# Rat.net
KiCad netlist of a schematic drawn in EAGLE
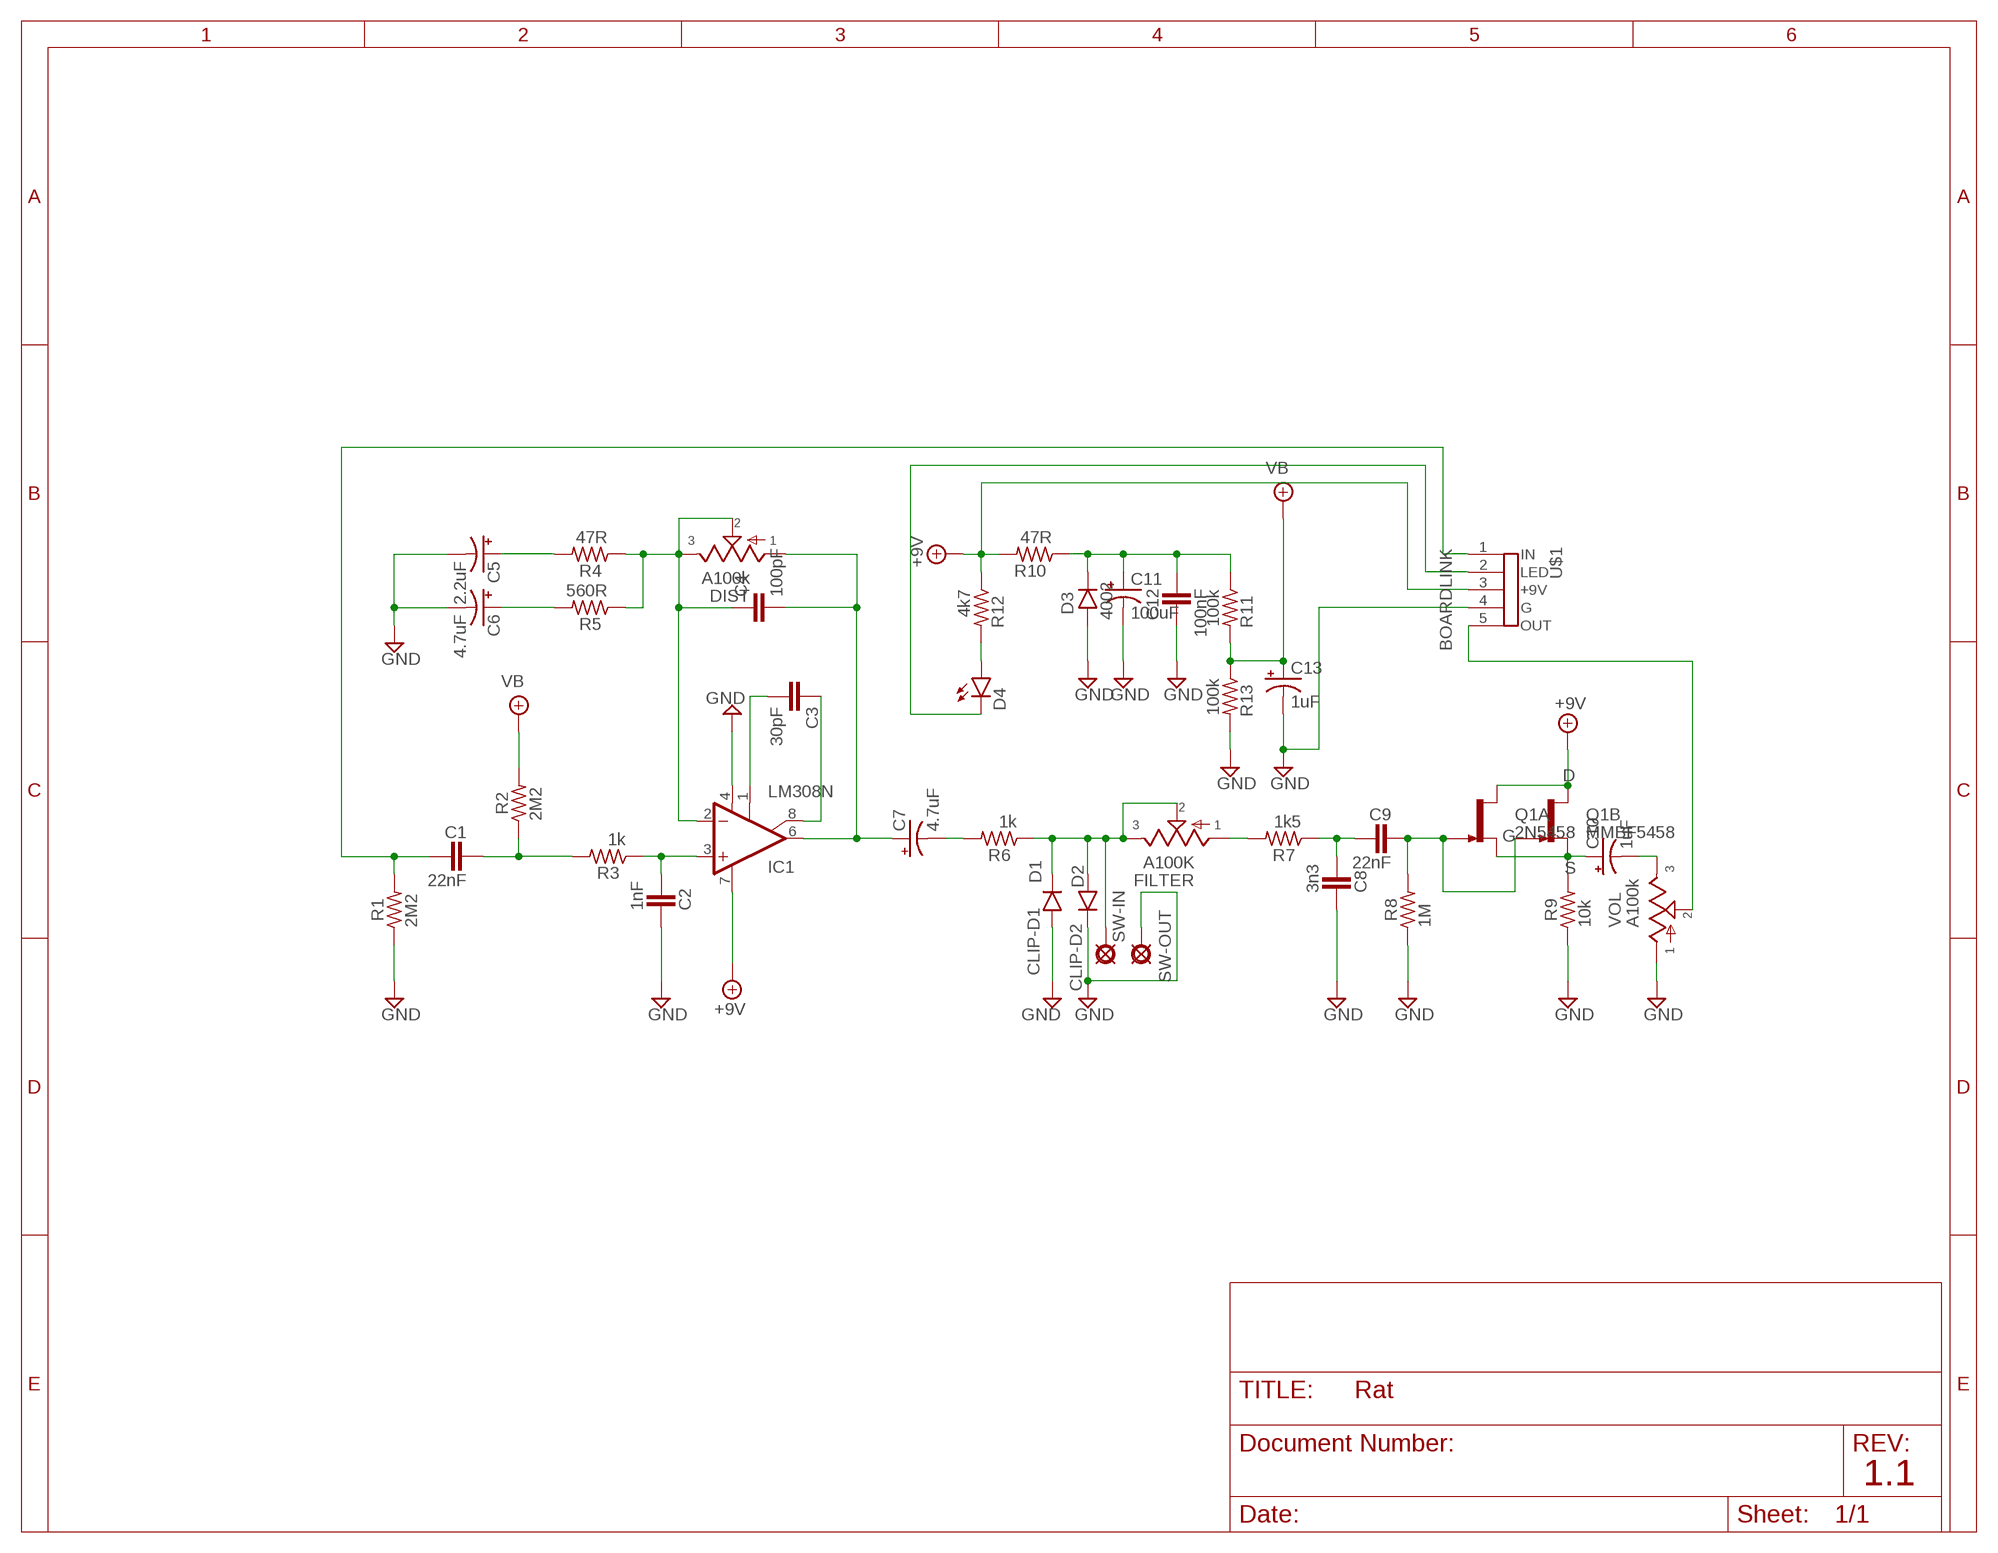
[diagram p0: schematic, sheet 1]

(export (version "E")
  (design (tool "Eeschema 10.0.6"))
  (components
    (comp (ref "C1")
      (value "22nF")
      (footprint "eagle-import:072X025")
      (libsource (lib "eagle-import") (part "072X0252"))
    )
    (comp (ref "C2")
      (value "1nF")
      (footprint "eagle-import:072X025")
      (libsource (lib "eagle-import") (part "072X0252"))
    )
    (comp (ref "C3")
      (value "30pF")
      (footprint "eagle-import:050X030_025")
      (libsource (lib "eagle-import") (part "050X030_0251"))
    )
    (comp (ref "C4")
      (value "100pF")
      (footprint "eagle-import:050X030_025")
      (libsource (lib "eagle-import") (part "050X030_0251"))
    )
    (comp (ref "C5")
      (value "2.2uF")
      (footprint "eagle-import:050_020_1")
      (libsource (lib "eagle-import") (part "0501"))
    )
    (comp (ref "C6")
      (value "4.7uF")
      (footprint "eagle-import:050_020_1")
      (libsource (lib "eagle-import") (part "0501"))
    )
    (comp (ref "C7")
      (value "4.7uF")
      (footprint "eagle-import:050_020_1")
      (libsource (lib "eagle-import") (part "0501"))
    )
    (comp (ref "C8")
      (value "3n3")
      (footprint "eagle-import:072X025")
      (libsource (lib "eagle-import") (part "072X0252"))
    )
    (comp (ref "C9")
      (value "22nF")
      (footprint "eagle-import:072X025")
      (libsource (lib "eagle-import") (part "072X0252"))
    )
    (comp (ref "C10")
      (value "1uF")
      (footprint "eagle-import:050_020_1")
      (libsource (lib "eagle-import") (part "0501"))
    )
    (comp (ref "C11")
      (value "100uF")
      (footprint "eagle-import:080_035_1")
      (libsource (lib "eagle-import") (part "0801"))
    )
    (comp (ref "C12")
      (value "100nF")
      (footprint "eagle-import:072X025")
      (libsource (lib "eagle-import") (part "072X0252"))
    )
    (comp (ref "C13")
      (value "1uF")
      (footprint "eagle-import:050_020_1")
      (libsource (lib "eagle-import") (part "0501"))
    )
    (comp (ref "D1")
      (value "CLIP-D1")
      (footprint "eagle-import:DO35-3")
      (libsource (lib "eagle-import") (part "1N914.3"))
    )
    (comp (ref "D2")
      (value "CLIP-D2")
      (footprint "eagle-import:DO35-3")
      (libsource (lib "eagle-import") (part "1N914.3"))
    )
    (comp (ref "D3")
      (value "4002")
      (footprint "eagle-import:DO41-3")
      (libsource (lib "eagle-import") (part "1N400X.3"))
    )
    (comp (ref "D4")
      (value "LED3MM")
      (footprint "eagle-import:LED3MM")
      (libsource (lib "eagle-import") (part "LED3MM"))
    )
    (comp (ref "DIST")
      (value "A100k")
      (footprint "eagle-import:16MM")
      (libsource (lib "eagle-import") (part "POT16MM"))
    )
    (comp (ref "FILTER")
      (value "A100K")
      (footprint "eagle-import:16MM")
      (libsource (lib "eagle-import") (part "POT16MM"))
    )
    (comp (ref "IC1")
      (value "LM308N")
      (footprint "eagle-import:DIL08")
      (libsource (lib "eagle-import") (part "LM308N"))
    )
    (comp (ref "Q1A")
      (value "2N5458")
      (footprint "eagle-import:TO92-")
      (libsource (lib "eagle-import") (part "2N5458"))
    )
    (comp (ref "Q1B")
      (value "MMBF5458")
      (footprint "eagle-import:SOT23")
      (libsource (lib "eagle-import") (part "MMBF5458"))
    )
    (comp (ref "R1")
      (value "2M2")
      (footprint "eagle-import:R0207_3")
      (libsource (lib "eagle-import") (part "6MM.3"))
    )
    (comp (ref "R2")
      (value "2M2")
      (footprint "eagle-import:R0207_3")
      (libsource (lib "eagle-import") (part "6MM.3"))
    )
    (comp (ref "R3")
      (value "1k")
      (footprint "eagle-import:R0207_3")
      (libsource (lib "eagle-import") (part "6MM.3"))
    )
    (comp (ref "R4")
      (value "47R")
      (footprint "eagle-import:R0207_3")
      (libsource (lib "eagle-import") (part "6MM.3"))
    )
    (comp (ref "R5")
      (value "560R")
      (footprint "eagle-import:R0207_3")
      (libsource (lib "eagle-import") (part "6MM.3"))
    )
    (comp (ref "R6")
      (value "1k")
      (footprint "eagle-import:R0207_3")
      (libsource (lib "eagle-import") (part "6MM.3"))
    )
    (comp (ref "R7")
      (value "1k5")
      (footprint "eagle-import:R0207_3")
      (libsource (lib "eagle-import") (part "6MM.3"))
    )
    (comp (ref "R8")
      (value "1M")
      (footprint "eagle-import:R0207_3")
      (libsource (lib "eagle-import") (part "6MM.3"))
    )
    (comp (ref "R9")
      (value "10k")
      (footprint "eagle-import:R0207_3")
      (libsource (lib "eagle-import") (part "6MM.3"))
    )
    (comp (ref "R10")
      (value "47R")
      (footprint "eagle-import:R0207_3")
      (libsource (lib "eagle-import") (part "6MM.3"))
    )
    (comp (ref "R11")
      (value "100k")
      (footprint "eagle-import:R0207_3")
      (libsource (lib "eagle-import") (part "6MM.3"))
    )
    (comp (ref "R12")
      (value "4k7")
      (footprint "eagle-import:R0207_3")
      (libsource (lib "eagle-import") (part "6MM.3"))
    )
    (comp (ref "R13")
      (value "100k")
      (footprint "eagle-import:R0207_3")
      (libsource (lib "eagle-import") (part "6MM.3"))
    )
    (comp (ref "SW-IN")
      (value "PAD")
      (footprint "eagle-import:SQUARE")
      (libsource (lib "eagle-import") (part "PAD"))
    )
    (comp (ref "SW-OUT")
      (value "PADO")
      (footprint "eagle-import:ROUND")
      (libsource (lib "eagle-import") (part "PADO"))
    )
    (comp (ref "U$1")
      (value "BOARDLINK")
      (footprint "eagle-import:BOARDLINK")
      (libsource (lib "eagle-import") (part "BOARDLINK"))
    )
    (comp (ref "VOL")
      (value "A100k")
      (footprint "eagle-import:16MM")
      (libsource (lib "eagle-import") (part "POT16MM"))
    )
  )
  (nets
    (net (code "1") (name "+9V") (class "Default")
      (node (ref "IC1") (pin "7") (pinfunction "V+_7") (pintype "power_in"))
      (node (ref "Q1A") (pin "3") (pinfunction "D_3") (pintype "passive"))
      (node (ref "Q1B") (pin "1") (pinfunction "D_1") (pintype "passive"))
      (node (ref "R10") (pin "2") (pinfunction "2_2") (pintype "passive"))
      (node (ref "R12") (pin "1") (pinfunction "1_1") (pintype "passive"))
      (node (ref "U$1") (pin "3") (pinfunction "+9V_3") (pintype "bidirectional"))
    )
    (net (code "2") (name "GND") (class "Default")
      (node (ref "C11") (pin "-") (pinfunction "-_-") (pintype "passive"))
      (node (ref "C12") (pin "1") (pinfunction "1_1") (pintype "passive"))
      (node (ref "C13") (pin "-") (pinfunction "-_-") (pintype "passive"))
      (node (ref "C2") (pin "2") (pinfunction "2_2") (pintype "passive"))
      (node (ref "C5") (pin "-") (pinfunction "-_-") (pintype "passive"))
      (node (ref "C6") (pin "-") (pinfunction "-_-") (pintype "passive"))
      (node (ref "C8") (pin "2") (pinfunction "2_2") (pintype "passive"))
      (node (ref "D1") (pin "A") (pinfunction "A_A") (pintype "passive"))
      (node (ref "D2") (pin "C") (pinfunction "C_C") (pintype "passive"))
      (node (ref "D3") (pin "A") (pinfunction "A_A") (pintype "passive"))
      (node (ref "IC1") (pin "4") (pinfunction "V-_4") (pintype "power_in"))
      (node (ref "R1") (pin "1") (pinfunction "1_1") (pintype "passive"))
      (node (ref "R13") (pin "2") (pinfunction "2_2") (pintype "passive"))
      (node (ref "R8") (pin "1") (pinfunction "1_1") (pintype "passive"))
      (node (ref "R9") (pin "1") (pinfunction "1_1") (pintype "passive"))
      (node (ref "SW-OUT") (pin "1") (pinfunction "PAD_1") (pintype "passive"))
      (node (ref "U$1") (pin "4") (pinfunction "G_4") (pintype "bidirectional"))
      (node (ref "VOL") (pin "1") (pinfunction "1_1") (pintype "passive"))
    )
    (net (code "3") (name "Net-(C1-Pad2)") (class "Default")
      (node (ref "C1") (pin "2") (pinfunction "2_2") (pintype "passive"))
      (node (ref "R2") (pin "1") (pinfunction "1_1") (pintype "passive"))
      (node (ref "R3") (pin "2") (pinfunction "2_2") (pintype "passive"))
    )
    (net (code "4") (name "Net-(C5-Pad+)") (class "Default")
      (node (ref "C5") (pin "+") (pinfunction "+_+") (pintype "passive"))
      (node (ref "R4") (pin "2") (pinfunction "2_2") (pintype "passive"))
    )
    (net (code "5") (name "Net-(C6-Pad+)") (class "Default")
      (node (ref "C6") (pin "+") (pinfunction "+_+") (pintype "passive"))
      (node (ref "R5") (pin "2") (pinfunction "2_2") (pintype "passive"))
    )
    (net (code "6") (name "Net-(C7-Pad-)") (class "Default")
      (node (ref "C7") (pin "-") (pinfunction "-_-") (pintype "passive"))
      (node (ref "R6") (pin "2") (pinfunction "2_2") (pintype "passive"))
    )
    (net (code "7") (name "Net-(C8-Pad1)") (class "Default")
      (node (ref "C8") (pin "1") (pinfunction "1_1") (pintype "passive"))
      (node (ref "C9") (pin "1") (pinfunction "1_1") (pintype "passive"))
      (node (ref "R7") (pin "1") (pinfunction "1_1") (pintype "passive"))
    )
    (net (code "8") (name "Net-(C10-Pad-)") (class "Default")
      (node (ref "C10") (pin "-") (pinfunction "-_-") (pintype "passive"))
      (node (ref "VOL") (pin "3") (pinfunction "3_3") (pintype "passive"))
    )
    (net (code "9") (name "Net-(C11-Pad+)") (class "Default")
      (node (ref "C11") (pin "+") (pinfunction "+_+") (pintype "passive"))
      (node (ref "C12") (pin "2") (pinfunction "2_2") (pintype "passive"))
      (node (ref "D3") (pin "C") (pinfunction "C_C") (pintype "passive"))
      (node (ref "R10") (pin "1") (pinfunction "1_1") (pintype "passive"))
      (node (ref "R11") (pin "1") (pinfunction "1_1") (pintype "passive"))
    )
    (net (code "10") (name "Net-(D4-C)") (class "Default")
      (node (ref "D4") (pin "K") (pinfunction "C_K") (pintype "passive"))
      (node (ref "U$1") (pin "2") (pinfunction "LED_2") (pintype "bidirectional"))
    )
    (net (code "11") (name "Net-(D4-PadA)") (class "Default")
      (node (ref "D4") (pin "A") (pinfunction "A_A") (pintype "passive"))
      (node (ref "R12") (pin "2") (pinfunction "2_2") (pintype "passive"))
    )
    (net (code "12") (name "Net-(FILTER-Pad1)") (class "Default")
      (node (ref "FILTER") (pin "1") (pinfunction "1_1") (pintype "passive"))
      (node (ref "R7") (pin "2") (pinfunction "2_2") (pintype "passive"))
    )
    (net (code "13") (name "Net-(IC1-+IN)") (class "Default")
      (node (ref "C2") (pin "1") (pinfunction "1_1") (pintype "passive"))
      (node (ref "IC1") (pin "3") (pinfunction "+IN_3") (pintype "input"))
      (node (ref "R3") (pin "1") (pinfunction "1_1") (pintype "passive"))
    )
    (net (code "14") (name "Net-(IC1--IN)") (class "Default")
      (node (ref "C4") (pin "1") (pinfunction "1_1") (pintype "passive"))
      (node (ref "DIST") (pin "2") (pinfunction "2_2") (pintype "passive"))
      (node (ref "DIST") (pin "3") (pinfunction "3_3") (pintype "passive"))
      (node (ref "IC1") (pin "2") (pinfunction "-IN_2") (pintype "input"))
      (node (ref "R4") (pin "1") (pinfunction "1_1") (pintype "passive"))
      (node (ref "R5") (pin "1") (pinfunction "1_1") (pintype "passive"))
    )
    (net (code "15") (name "Net-(IC1-CMP1)") (class "Default")
      (node (ref "C3") (pin "2") (pinfunction "2_2") (pintype "passive"))
      (node (ref "IC1") (pin "1") (pinfunction "CMP1_1") (pintype "passive"))
    )
    (net (code "16") (name "Net-(IC1-CMP2)") (class "Default")
      (node (ref "C3") (pin "1") (pinfunction "1_1") (pintype "passive"))
      (node (ref "IC1") (pin "8") (pinfunction "CMP2_8") (pintype "passive"))
    )
    (net (code "17") (name "Net-(IC1-OUT)") (class "Default")
      (node (ref "C4") (pin "2") (pinfunction "2_2") (pintype "passive"))
      (node (ref "C7") (pin "+") (pinfunction "+_+") (pintype "passive"))
      (node (ref "DIST") (pin "1") (pinfunction "1_1") (pintype "passive"))
      (node (ref "IC1") (pin "6") (pinfunction "OUT_6") (pintype "output"))
    )
    (net (code "18") (name "Net-(Q1A-G)") (class "Default")
      (node (ref "C9") (pin "2") (pinfunction "2_2") (pintype "passive"))
      (node (ref "Q1A") (pin "1") (pinfunction "G_1") (pintype "passive"))
      (node (ref "Q1B") (pin "3") (pinfunction "G_3") (pintype "passive"))
      (node (ref "R8") (pin "2") (pinfunction "2_2") (pintype "passive"))
    )
    (net (code "19") (name "Net-(Q1A-S)") (class "Default")
      (node (ref "C10") (pin "+") (pinfunction "+_+") (pintype "passive"))
      (node (ref "Q1A") (pin "2") (pinfunction "S_2") (pintype "passive"))
      (node (ref "Q1B") (pin "2") (pinfunction "S_2") (pintype "passive"))
      (node (ref "R9") (pin "2") (pinfunction "2_2") (pintype "passive"))
    )
    (net (code "20") (name "Net-(SW-IN-PAD)") (class "Default")
      (node (ref "D1") (pin "C") (pinfunction "C_C") (pintype "passive"))
      (node (ref "D2") (pin "A") (pinfunction "A_A") (pintype "passive"))
      (node (ref "FILTER") (pin "2") (pinfunction "2_2") (pintype "passive"))
      (node (ref "FILTER") (pin "3") (pinfunction "3_3") (pintype "passive"))
      (node (ref "R6") (pin "1") (pinfunction "1_1") (pintype "passive"))
      (node (ref "SW-IN") (pin "1") (pinfunction "PAD_1") (pintype "passive"))
    )
    (net (code "21") (name "Net-(U$1-IN)") (class "Default")
      (node (ref "C1") (pin "1") (pinfunction "1_1") (pintype "passive"))
      (node (ref "R1") (pin "2") (pinfunction "2_2") (pintype "passive"))
      (node (ref "U$1") (pin "1") (pinfunction "IN_1") (pintype "bidirectional"))
    )
    (net (code "22") (name "Net-(U$1-OUT)") (class "Default")
      (node (ref "U$1") (pin "5") (pinfunction "OUT_5") (pintype "bidirectional"))
      (node (ref "VOL") (pin "2") (pinfunction "2_2") (pintype "passive"))
    )
    (net (code "23") (name "VB") (class "Default")
      (node (ref "C13") (pin "+") (pinfunction "+_+") (pintype "passive"))
      (node (ref "R11") (pin "2") (pinfunction "2_2") (pintype "passive"))
      (node (ref "R13") (pin "1") (pinfunction "1_1") (pintype "passive"))
      (node (ref "R2") (pin "2") (pinfunction "2_2") (pintype "passive"))
    )
  )
)
